# generic_pod.net
KiCad netlist of a schematic drawn in EAGLE
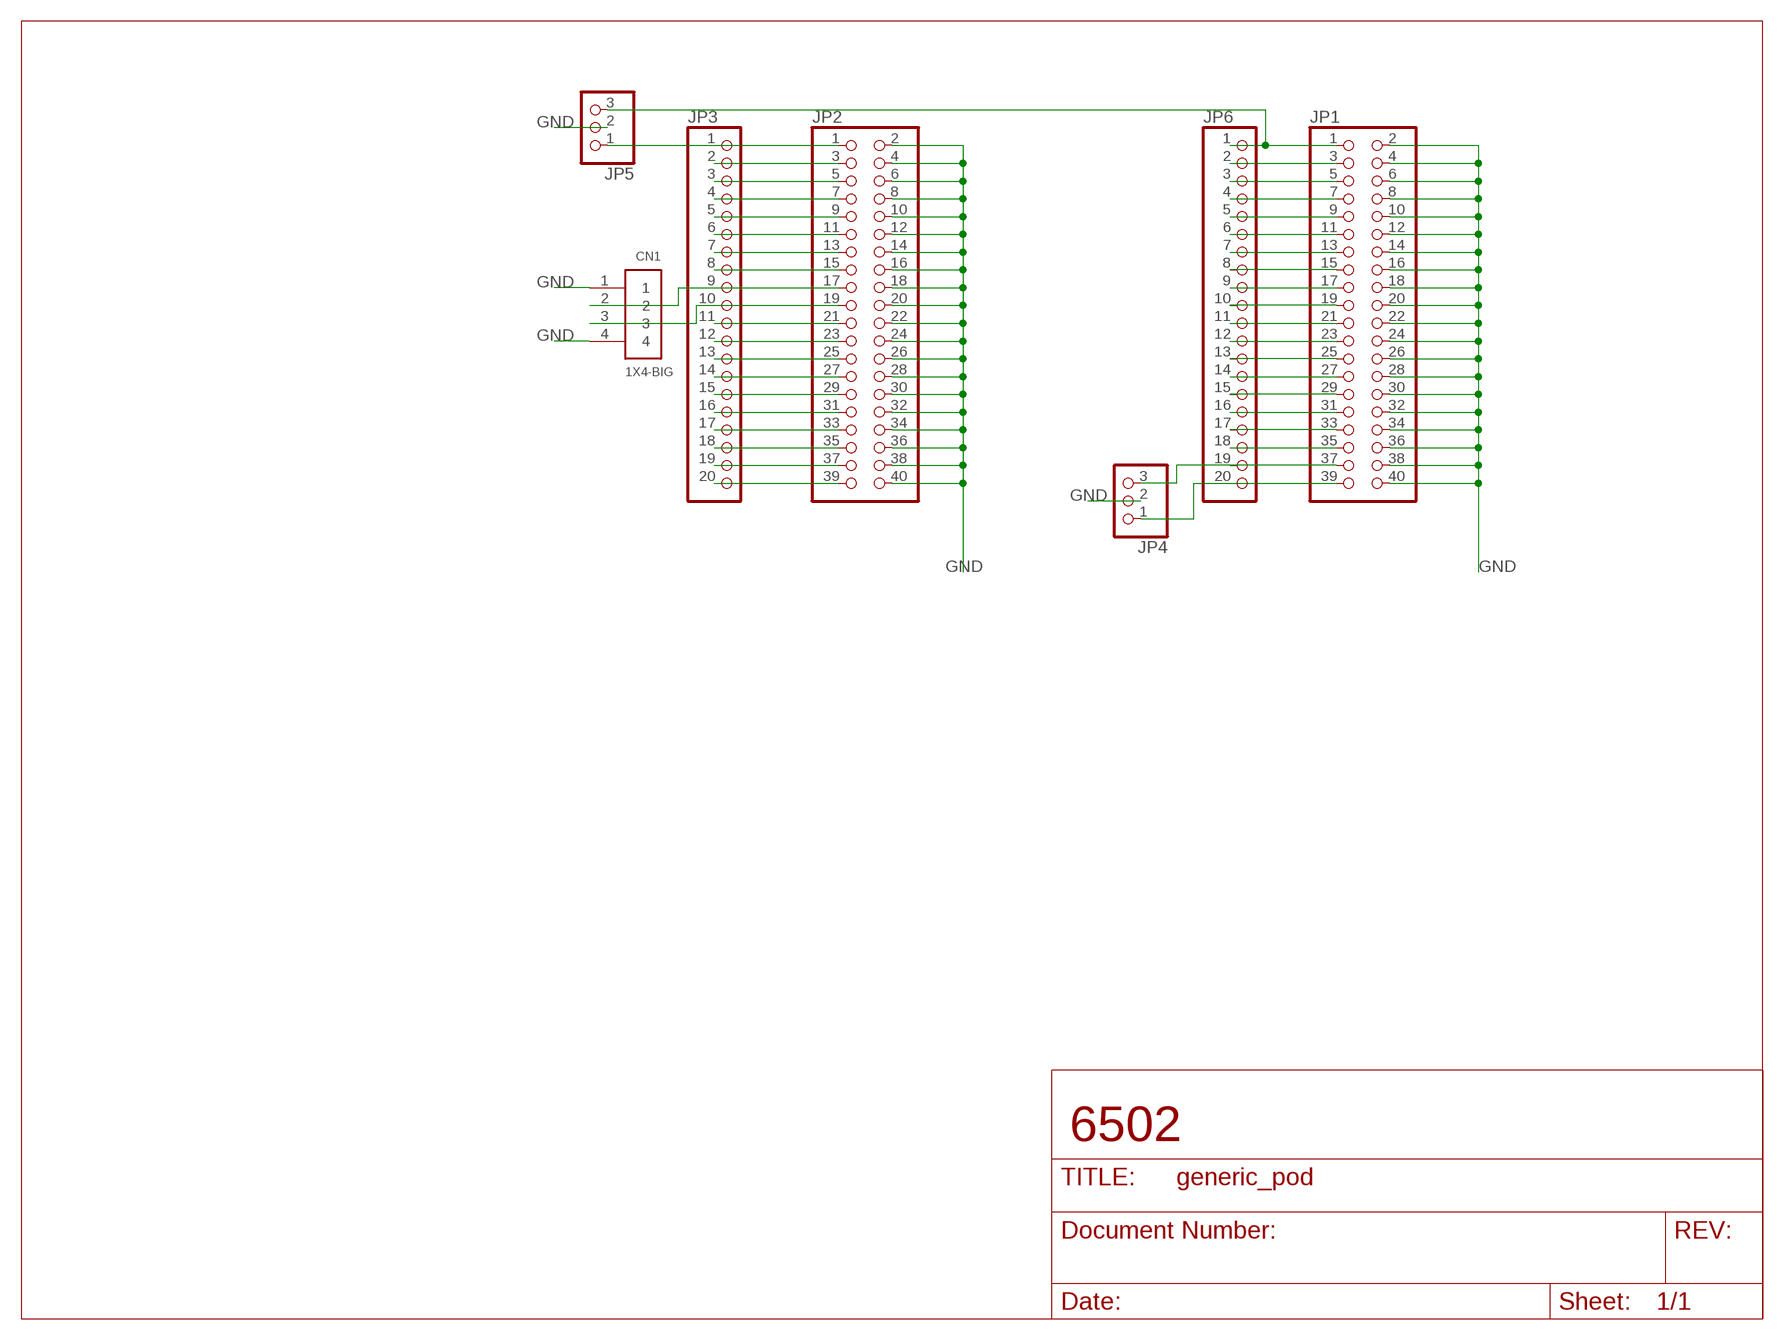
[diagram p0: schematic, sheet 1]

(export (version "E")
  (design (tool "Eeschema 10.0.6"))
  (components
    (comp (ref "CN1")
      (value "1X4-BIG")
      (footprint "eagle-import:1X04-BIG")
      (libsource (lib "eagle-import") (part "1X4-BIG"))
    )
    (comp (ref "JP1")
      (value "PINHD-2X20-BIG")
      (footprint "eagle-import:2X20-BIG")
      (libsource (lib "eagle-import") (part "PINHD-2X20-BIG"))
    )
    (comp (ref "JP2")
      (value "PINHD-2X20-BIG")
      (footprint "eagle-import:2X20-BIG")
      (libsource (lib "eagle-import") (part "PINHD-2X20-BIG"))
    )
    (comp (ref "JP3")
      (value "PINHD-1X20-BIG")
      (footprint "eagle-import:1X20-BIG")
      (libsource (lib "eagle-import") (part "PINHD-1X20-BIG"))
    )
    (comp (ref "JP4")
      (value "PINHD-1X3")
      (footprint "eagle-import:1X03")
      (libsource (lib "eagle-import") (part "PINHD-1X3"))
    )
    (comp (ref "JP5")
      (value "PINHD-1X3")
      (footprint "eagle-import:1X03")
      (libsource (lib "eagle-import") (part "PINHD-1X3"))
    )
    (comp (ref "JP6")
      (value "PINHD-1X20-BIG")
      (footprint "eagle-import:1X20-BIG")
      (libsource (lib "eagle-import") (part "PINHD-1X20-BIG"))
    )
  )
  (nets
    (net (code "1") (name "/GND") (class "Default")
      (node (ref "CN1") (pin "1") (pinfunction "1_1") (pintype "bidirectional"))
      (node (ref "CN1") (pin "4") (pinfunction "4_4") (pintype "bidirectional"))
      (node (ref "JP1") (pin "10") (pinfunction "10_10") (pintype "passive"))
      (node (ref "JP1") (pin "12") (pinfunction "12_12") (pintype "passive"))
      (node (ref "JP1") (pin "14") (pinfunction "14_14") (pintype "passive"))
      (node (ref "JP1") (pin "16") (pinfunction "16_16") (pintype "passive"))
      (node (ref "JP1") (pin "18") (pinfunction "18_18") (pintype "passive"))
      (node (ref "JP1") (pin "2") (pinfunction "2_2") (pintype "passive"))
      (node (ref "JP1") (pin "20") (pinfunction "20_20") (pintype "passive"))
      (node (ref "JP1") (pin "22") (pinfunction "22_22") (pintype "passive"))
      (node (ref "JP1") (pin "24") (pinfunction "24_24") (pintype "passive"))
      (node (ref "JP1") (pin "26") (pinfunction "26_26") (pintype "passive"))
      (node (ref "JP1") (pin "28") (pinfunction "28_28") (pintype "passive"))
      (node (ref "JP1") (pin "30") (pinfunction "30_30") (pintype "passive"))
      (node (ref "JP1") (pin "32") (pinfunction "32_32") (pintype "passive"))
      (node (ref "JP1") (pin "34") (pinfunction "34_34") (pintype "passive"))
      (node (ref "JP1") (pin "36") (pinfunction "36_36") (pintype "passive"))
      (node (ref "JP1") (pin "38") (pinfunction "38_38") (pintype "passive"))
      (node (ref "JP1") (pin "4") (pinfunction "4_4") (pintype "passive"))
      (node (ref "JP1") (pin "40") (pinfunction "40_40") (pintype "passive"))
      (node (ref "JP1") (pin "6") (pinfunction "6_6") (pintype "passive"))
      (node (ref "JP1") (pin "8") (pinfunction "8_8") (pintype "passive"))
      (node (ref "JP2") (pin "10") (pinfunction "10_10") (pintype "passive"))
      (node (ref "JP2") (pin "12") (pinfunction "12_12") (pintype "passive"))
      (node (ref "JP2") (pin "14") (pinfunction "14_14") (pintype "passive"))
      (node (ref "JP2") (pin "16") (pinfunction "16_16") (pintype "passive"))
      (node (ref "JP2") (pin "18") (pinfunction "18_18") (pintype "passive"))
      (node (ref "JP2") (pin "2") (pinfunction "2_2") (pintype "passive"))
      (node (ref "JP2") (pin "20") (pinfunction "20_20") (pintype "passive"))
      (node (ref "JP2") (pin "22") (pinfunction "22_22") (pintype "passive"))
      (node (ref "JP2") (pin "24") (pinfunction "24_24") (pintype "passive"))
      (node (ref "JP2") (pin "26") (pinfunction "26_26") (pintype "passive"))
      (node (ref "JP2") (pin "28") (pinfunction "28_28") (pintype "passive"))
      (node (ref "JP2") (pin "30") (pinfunction "30_30") (pintype "passive"))
      (node (ref "JP2") (pin "32") (pinfunction "32_32") (pintype "passive"))
      (node (ref "JP2") (pin "34") (pinfunction "34_34") (pintype "passive"))
      (node (ref "JP2") (pin "36") (pinfunction "36_36") (pintype "passive"))
      (node (ref "JP2") (pin "38") (pinfunction "38_38") (pintype "passive"))
      (node (ref "JP2") (pin "4") (pinfunction "4_4") (pintype "passive"))
      (node (ref "JP2") (pin "40") (pinfunction "40_40") (pintype "passive"))
      (node (ref "JP2") (pin "6") (pinfunction "6_6") (pintype "passive"))
      (node (ref "JP2") (pin "8") (pinfunction "8_8") (pintype "passive"))
      (node (ref "JP4") (pin "2") (pinfunction "2_2") (pintype "passive"))
      (node (ref "JP5") (pin "2") (pinfunction "2_2") (pintype "passive"))
    )
    (net (code "2") (name "Net-(CN1-Pad2)") (class "Default")
      (node (ref "CN1") (pin "2") (pinfunction "2_2") (pintype "bidirectional"))
      (node (ref "JP2") (pin "17") (pinfunction "17_17") (pintype "passive"))
      (node (ref "JP3") (pin "9") (pinfunction "9_9") (pintype "passive"))
    )
    (net (code "3") (name "Net-(CN1-Pad3)") (class "Default")
      (node (ref "CN1") (pin "3") (pinfunction "3_3") (pintype "bidirectional"))
      (node (ref "JP2") (pin "19") (pinfunction "19_19") (pintype "passive"))
      (node (ref "JP3") (pin "10") (pinfunction "10_10") (pintype "passive"))
    )
    (net (code "4") (name "Net-(JP1-Pad1)") (class "Default")
      (node (ref "JP1") (pin "1") (pinfunction "1_1") (pintype "passive"))
      (node (ref "JP5") (pin "3") (pinfunction "3_3") (pintype "passive"))
      (node (ref "JP6") (pin "1") (pinfunction "1_1") (pintype "passive"))
    )
    (net (code "5") (name "Net-(JP1-Pad3)") (class "Default")
      (node (ref "JP1") (pin "3") (pinfunction "3_3") (pintype "passive"))
      (node (ref "JP6") (pin "2") (pinfunction "2_2") (pintype "passive"))
    )
    (net (code "6") (name "Net-(JP1-Pad5)") (class "Default")
      (node (ref "JP1") (pin "5") (pinfunction "5_5") (pintype "passive"))
      (node (ref "JP6") (pin "3") (pinfunction "3_3") (pintype "passive"))
    )
    (net (code "7") (name "Net-(JP1-Pad7)") (class "Default")
      (node (ref "JP1") (pin "7") (pinfunction "7_7") (pintype "passive"))
      (node (ref "JP6") (pin "4") (pinfunction "4_4") (pintype "passive"))
    )
    (net (code "8") (name "Net-(JP1-Pad9)") (class "Default")
      (node (ref "JP1") (pin "9") (pinfunction "9_9") (pintype "passive"))
      (node (ref "JP6") (pin "5") (pinfunction "5_5") (pintype "passive"))
    )
    (net (code "9") (name "Net-(JP1-Pad11)") (class "Default")
      (node (ref "JP1") (pin "11") (pinfunction "11_11") (pintype "passive"))
      (node (ref "JP6") (pin "6") (pinfunction "6_6") (pintype "passive"))
    )
    (net (code "10") (name "Net-(JP1-Pad13)") (class "Default")
      (node (ref "JP1") (pin "13") (pinfunction "13_13") (pintype "passive"))
      (node (ref "JP6") (pin "7") (pinfunction "7_7") (pintype "passive"))
    )
    (net (code "11") (name "Net-(JP1-Pad15)") (class "Default")
      (node (ref "JP1") (pin "15") (pinfunction "15_15") (pintype "passive"))
      (node (ref "JP6") (pin "8") (pinfunction "8_8") (pintype "passive"))
    )
    (net (code "12") (name "Net-(JP1-Pad17)") (class "Default")
      (node (ref "JP1") (pin "17") (pinfunction "17_17") (pintype "passive"))
      (node (ref "JP6") (pin "9") (pinfunction "9_9") (pintype "passive"))
    )
    (net (code "13") (name "Net-(JP1-Pad19)") (class "Default")
      (node (ref "JP1") (pin "19") (pinfunction "19_19") (pintype "passive"))
      (node (ref "JP6") (pin "10") (pinfunction "10_10") (pintype "passive"))
    )
    (net (code "14") (name "Net-(JP1-Pad21)") (class "Default")
      (node (ref "JP1") (pin "21") (pinfunction "21_21") (pintype "passive"))
      (node (ref "JP6") (pin "11") (pinfunction "11_11") (pintype "passive"))
    )
    (net (code "15") (name "Net-(JP1-Pad23)") (class "Default")
      (node (ref "JP1") (pin "23") (pinfunction "23_23") (pintype "passive"))
      (node (ref "JP6") (pin "12") (pinfunction "12_12") (pintype "passive"))
    )
    (net (code "16") (name "Net-(JP1-Pad25)") (class "Default")
      (node (ref "JP1") (pin "25") (pinfunction "25_25") (pintype "passive"))
      (node (ref "JP6") (pin "13") (pinfunction "13_13") (pintype "passive"))
    )
    (net (code "17") (name "Net-(JP1-Pad27)") (class "Default")
      (node (ref "JP1") (pin "27") (pinfunction "27_27") (pintype "passive"))
      (node (ref "JP6") (pin "14") (pinfunction "14_14") (pintype "passive"))
    )
    (net (code "18") (name "Net-(JP1-Pad29)") (class "Default")
      (node (ref "JP1") (pin "29") (pinfunction "29_29") (pintype "passive"))
      (node (ref "JP6") (pin "15") (pinfunction "15_15") (pintype "passive"))
    )
    (net (code "19") (name "Net-(JP1-Pad31)") (class "Default")
      (node (ref "JP1") (pin "31") (pinfunction "31_31") (pintype "passive"))
      (node (ref "JP6") (pin "16") (pinfunction "16_16") (pintype "passive"))
    )
    (net (code "20") (name "Net-(JP1-Pad33)") (class "Default")
      (node (ref "JP1") (pin "33") (pinfunction "33_33") (pintype "passive"))
      (node (ref "JP6") (pin "17") (pinfunction "17_17") (pintype "passive"))
    )
    (net (code "21") (name "Net-(JP1-Pad35)") (class "Default")
      (node (ref "JP1") (pin "35") (pinfunction "35_35") (pintype "passive"))
      (node (ref "JP6") (pin "18") (pinfunction "18_18") (pintype "passive"))
    )
    (net (code "22") (name "Net-(JP1-Pad37)") (class "Default")
      (node (ref "JP1") (pin "37") (pinfunction "37_37") (pintype "passive"))
      (node (ref "JP4") (pin "3") (pinfunction "3_3") (pintype "passive"))
      (node (ref "JP6") (pin "19") (pinfunction "19_19") (pintype "passive"))
    )
    (net (code "23") (name "Net-(JP1-Pad39)") (class "Default")
      (node (ref "JP1") (pin "39") (pinfunction "39_39") (pintype "passive"))
      (node (ref "JP4") (pin "1") (pinfunction "1_1") (pintype "passive"))
      (node (ref "JP6") (pin "20") (pinfunction "20_20") (pintype "passive"))
    )
    (net (code "24") (name "Net-(JP2-Pad1)") (class "Default")
      (node (ref "JP2") (pin "1") (pinfunction "1_1") (pintype "passive"))
      (node (ref "JP3") (pin "1") (pinfunction "1_1") (pintype "passive"))
      (node (ref "JP5") (pin "1") (pinfunction "1_1") (pintype "passive"))
    )
    (net (code "25") (name "Net-(JP2-Pad3)") (class "Default")
      (node (ref "JP2") (pin "3") (pinfunction "3_3") (pintype "passive"))
      (node (ref "JP3") (pin "2") (pinfunction "2_2") (pintype "passive"))
    )
    (net (code "26") (name "Net-(JP2-Pad5)") (class "Default")
      (node (ref "JP2") (pin "5") (pinfunction "5_5") (pintype "passive"))
      (node (ref "JP3") (pin "3") (pinfunction "3_3") (pintype "passive"))
    )
    (net (code "27") (name "Net-(JP2-Pad7)") (class "Default")
      (node (ref "JP2") (pin "7") (pinfunction "7_7") (pintype "passive"))
      (node (ref "JP3") (pin "4") (pinfunction "4_4") (pintype "passive"))
    )
    (net (code "28") (name "Net-(JP2-Pad9)") (class "Default")
      (node (ref "JP2") (pin "9") (pinfunction "9_9") (pintype "passive"))
      (node (ref "JP3") (pin "5") (pinfunction "5_5") (pintype "passive"))
    )
    (net (code "29") (name "Net-(JP2-Pad11)") (class "Default")
      (node (ref "JP2") (pin "11") (pinfunction "11_11") (pintype "passive"))
      (node (ref "JP3") (pin "6") (pinfunction "6_6") (pintype "passive"))
    )
    (net (code "30") (name "Net-(JP2-Pad13)") (class "Default")
      (node (ref "JP2") (pin "13") (pinfunction "13_13") (pintype "passive"))
      (node (ref "JP3") (pin "7") (pinfunction "7_7") (pintype "passive"))
    )
    (net (code "31") (name "Net-(JP2-Pad15)") (class "Default")
      (node (ref "JP2") (pin "15") (pinfunction "15_15") (pintype "passive"))
      (node (ref "JP3") (pin "8") (pinfunction "8_8") (pintype "passive"))
    )
    (net (code "32") (name "Net-(JP2-Pad21)") (class "Default")
      (node (ref "JP2") (pin "21") (pinfunction "21_21") (pintype "passive"))
      (node (ref "JP3") (pin "11") (pinfunction "11_11") (pintype "passive"))
    )
    (net (code "33") (name "Net-(JP2-Pad23)") (class "Default")
      (node (ref "JP2") (pin "23") (pinfunction "23_23") (pintype "passive"))
      (node (ref "JP3") (pin "12") (pinfunction "12_12") (pintype "passive"))
    )
    (net (code "34") (name "Net-(JP2-Pad25)") (class "Default")
      (node (ref "JP2") (pin "25") (pinfunction "25_25") (pintype "passive"))
      (node (ref "JP3") (pin "13") (pinfunction "13_13") (pintype "passive"))
    )
    (net (code "35") (name "Net-(JP2-Pad27)") (class "Default")
      (node (ref "JP2") (pin "27") (pinfunction "27_27") (pintype "passive"))
      (node (ref "JP3") (pin "14") (pinfunction "14_14") (pintype "passive"))
    )
    (net (code "36") (name "Net-(JP2-Pad29)") (class "Default")
      (node (ref "JP2") (pin "29") (pinfunction "29_29") (pintype "passive"))
      (node (ref "JP3") (pin "15") (pinfunction "15_15") (pintype "passive"))
    )
    (net (code "37") (name "Net-(JP2-Pad31)") (class "Default")
      (node (ref "JP2") (pin "31") (pinfunction "31_31") (pintype "passive"))
      (node (ref "JP3") (pin "16") (pinfunction "16_16") (pintype "passive"))
    )
    (net (code "38") (name "Net-(JP2-Pad33)") (class "Default")
      (node (ref "JP2") (pin "33") (pinfunction "33_33") (pintype "passive"))
      (node (ref "JP3") (pin "17") (pinfunction "17_17") (pintype "passive"))
    )
    (net (code "39") (name "Net-(JP2-Pad35)") (class "Default")
      (node (ref "JP2") (pin "35") (pinfunction "35_35") (pintype "passive"))
      (node (ref "JP3") (pin "18") (pinfunction "18_18") (pintype "passive"))
    )
    (net (code "40") (name "Net-(JP2-Pad37)") (class "Default")
      (node (ref "JP2") (pin "37") (pinfunction "37_37") (pintype "passive"))
      (node (ref "JP3") (pin "19") (pinfunction "19_19") (pintype "passive"))
    )
    (net (code "41") (name "Net-(JP2-Pad39)") (class "Default")
      (node (ref "JP2") (pin "39") (pinfunction "39_39") (pintype "passive"))
      (node (ref "JP3") (pin "20") (pinfunction "20_20") (pintype "passive"))
    )
  )
)
